# Sheet.net
KiCad netlist of a schematic drawn in Altium Designer
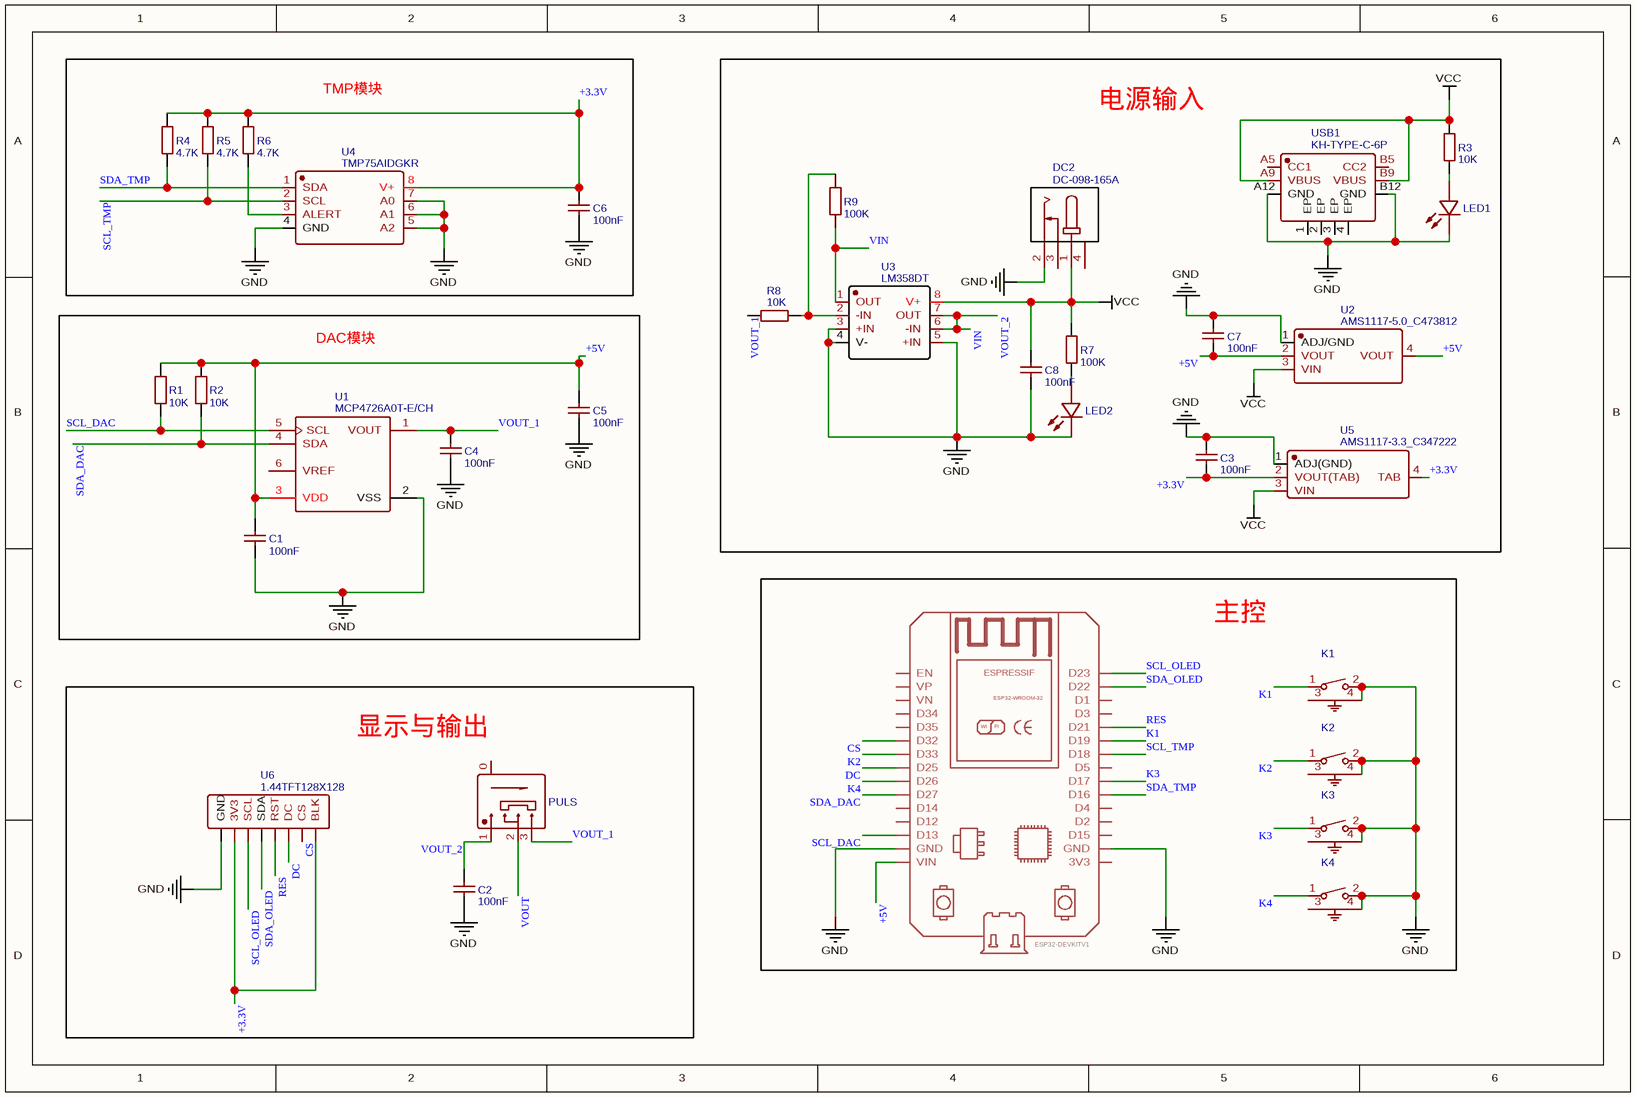
[diagram p0: Sheet.schdoc]

(export (version "E")
  (design (tool "Eeschema 10.0.6"))
  (components
    (comp (ref "BOARD1")
      (value "ESP32DEVKITV1")
      (fields (field (name "CONTRIBUTOR") "radio"))
      (libsource (lib "altium-import") (part "root_0_ESP32DEVKITV1_"))
    )
    (comp (ref "C1")
      (value "100nF")
      (fields
        (field (name "BOM_SUPPLIER PART") "C328914")
        (field (name "BOM_MANUFACTURER PART") "FN15X104K160PNG")
        (field (name "CONTRIBUTOR") "LCSC")
      )
      (libsource (lib "altium-import") (part "root_3_100nF_"))
    )
    (comp (ref "C2")
      (value "100nF")
      (fields
        (field (name "BOM_SUPPLIER PART") "C328914")
        (field (name "BOM_MANUFACTURER PART") "FN15X104K160PNG")
        (field (name "CONTRIBUTOR") "LCSC")
      )
      (libsource (lib "altium-import") (part "root_1_100nF_"))
    )
    (comp (ref "C3")
      (value "100nF")
      (fields
        (field (name "BOM_SUPPLIER PART") "C328914")
        (field (name "BOM_MANUFACTURER PART") "FN15X104K160PNG")
        (field (name "CONTRIBUTOR") "LCSC")
      )
      (libsource (lib "altium-import") (part "root_1_100nF_"))
    )
    (comp (ref "C4")
      (value "100nF")
      (fields
        (field (name "BOM_SUPPLIER PART") "C328914")
        (field (name "BOM_MANUFACTURER PART") "FN15X104K160PNG")
        (field (name "CONTRIBUTOR") "LCSC")
      )
      (libsource (lib "altium-import") (part "root_1_100nF_"))
    )
    (comp (ref "C5")
      (value "100nF")
      (fields
        (field (name "BOM_SUPPLIER PART") "C328914")
        (field (name "BOM_MANUFACTURER PART") "FN15X104K160PNG")
        (field (name "CONTRIBUTOR") "LCSC")
      )
      (libsource (lib "altium-import") (part "root_1_100nF_"))
    )
    (comp (ref "C6")
      (value "100nF")
      (fields
        (field (name "BOM_SUPPLIER PART") "C328914")
        (field (name "BOM_MANUFACTURER PART") "FN15X104K160PNG")
        (field (name "CONTRIBUTOR") "LCSC")
      )
      (libsource (lib "altium-import") (part "root_1_100nF_"))
    )
    (comp (ref "C7")
      (value "100nF")
      (fields
        (field (name "BOM_SUPPLIER PART") "C328914")
        (field (name "BOM_MANUFACTURER PART") "FN15X104K160PNG")
        (field (name "CONTRIBUTOR") "LCSC")
      )
      (libsource (lib "altium-import") (part "root_1_100nF_"))
    )
    (comp (ref "C8")
      (value "100nF")
      (fields
        (field (name "BOM_SUPPLIER PART") "C328914")
        (field (name "BOM_MANUFACTURER PART") "FN15X104K160PNG")
        (field (name "CONTRIBUTOR") "LCSC")
      )
      (libsource (lib "altium-import") (part "root_1_100nF_"))
    )
    (comp (ref "DC2")
      (value "DC-098-165A")
      (fields (field (name "BOM_SUPPLIER PART") "C129001") (field (name "CONTRIBUTOR") "LCSC"))
      (libsource (lib "altium-import") (part "root_3_DC-098-165A_"))
    )
    (comp (ref "K1")
      (value "KH-3635-CAJ")
      (fields (field (name "BOM_SUPPLIER PART") "C530670") (field (name "CONTRIBUTOR") "LCSC"))
      (libsource (lib "altium-import") (part "root_0_KH-3635-CAJ_"))
    )
    (comp (ref "K2")
      (value "KH-3635-CAJ")
      (fields (field (name "BOM_SUPPLIER PART") "C530670") (field (name "CONTRIBUTOR") "LCSC"))
      (libsource (lib "altium-import") (part "root_0_KH-3635-CAJ_"))
    )
    (comp (ref "K3")
      (value "KH-3635-CAJ")
      (fields (field (name "BOM_SUPPLIER PART") "C530670") (field (name "CONTRIBUTOR") "LCSC"))
      (libsource (lib "altium-import") (part "root_0_KH-3635-CAJ_"))
    )
    (comp (ref "K4")
      (value "KH-3635-CAJ")
      (fields (field (name "BOM_SUPPLIER PART") "C530670") (field (name "CONTRIBUTOR") "LCSC"))
      (libsource (lib "altium-import") (part "root_0_KH-3635-CAJ_"))
    )
    (comp (ref "LED1")
      (value "17-21SYGC/S530-E3/TR8")
      (fields (field (name "BOM_SUPPLIER PART") "C142303") (field (name "CONTRIBUTOR") "LCSC"))
      (libsource (lib "altium-import") (part "root_1_17-21SYGC/S530-E3/TR8_"))
    )
    (comp (ref "LED2")
      (value "17-21SURC/S530-A2/TR8")
      (fields (field (name "BOM_SUPPLIER PART") "C131244") (field (name "CONTRIBUTOR") "LCSC"))
      (libsource (lib "altium-import") (part "root_1_17-21SURC/S530-A2/TR8_"))
    )
    (comp (ref "PULS")
      (value "SK-3296S-01-L1")
      (fields (field (name "BOM_SUPPLIER PART") "C319020") (field (name "CONTRIBUTOR") "LCSC"))
      (libsource (lib "altium-import") (part "root_1_SK-3296S-01-L1_"))
    )
    (comp (ref "R1")
      (value "10K")
      (fields
        (field (name "BOM_MANUFACTURER PART") "0402WGJ0472TCE")
        (field (name "BOM_SUPPLIER PART") "C25940")
      )
      (libsource (lib "altium-import") (part "root_3_10K_"))
    )
    (comp (ref "R2")
      (value "10K")
      (fields
        (field (name "BOM_MANUFACTURER PART") "0402WGJ0472TCE")
        (field (name "BOM_SUPPLIER PART") "C25940")
      )
      (libsource (lib "altium-import") (part "root_1_10K_"))
    )
    (comp (ref "R3")
      (value "10K")
      (fields
        (field (name "BOM_MANUFACTURER PART") "0603WAF1002T5E")
        (field (name "BOM_SUPPLIER PART") "C25804")
      )
      (libsource (lib "altium-import") (part "root_1_10K_"))
    )
    (comp (ref "R4")
      (value "4.7K")
      (fields
        (field (name "BOM_MANUFACTURER PART") "0402WGJ0472TCE")
        (field (name "BOM_SUPPLIER PART") "C25940")
      )
      (libsource (lib "altium-import") (part "root_1_4.7K_"))
    )
    (comp (ref "R5")
      (value "4.7K")
      (fields
        (field (name "BOM_MANUFACTURER PART") "0402WGJ0472TCE")
        (field (name "BOM_SUPPLIER PART") "C25940")
      )
      (libsource (lib "altium-import") (part "root_1_4.7K_"))
    )
    (comp (ref "R6")
      (value "4.7K")
      (fields
        (field (name "BOM_MANUFACTURER PART") "0402WGJ0472TCE")
        (field (name "BOM_SUPPLIER PART") "C25940")
      )
      (libsource (lib "altium-import") (part "root_1_4.7K_"))
    )
    (comp (ref "R7")
      (value "100K")
      (fields
        (field (name "BOM_MANUFACTURER PART") "0603WAJ0104T5E")
        (field (name "BOM_SUPPLIER PART") "C15458")
      )
      (libsource (lib "altium-import") (part "root_1_100K_"))
    )
    (comp (ref "R8")
      (value "10K")
      (fields
        (field (name "BOM_MANUFACTURER PART") "0603WAF1002T5E")
        (field (name "BOM_SUPPLIER PART") "C25804")
      )
      (libsource (lib "altium-import") (part "root_2_10K_"))
    )
    (comp (ref "R9")
      (value "100K")
      (fields
        (field (name "BOM_MANUFACTURER PART") "0603WAJ0104T5E")
        (field (name "BOM_SUPPLIER PART") "C15458")
      )
      (libsource (lib "altium-import") (part "root_1_100K_"))
    )
    (comp (ref "U1")
      (value "MCP4726A0T-E/CH")
      (fields (field (name "BOM_SUPPLIER PART") "C191581") (field (name "CONTRIBUTOR") "LCSC"))
      (libsource (lib "altium-import") (part "root_0_MCP4726A0T-E/CH_"))
    )
    (comp (ref "U2")
      (value "AMS1117-5.0_C473812")
      (fields
        (field (name "BOM_SUPPLIER PART") "C473812")
        (field (name "BOM_MANUFACTURER PART") "AMS1117-5.0")
        (field (name "CONTRIBUTOR") "LCSC")
      )
      (libsource (lib "altium-import") (part "root_0_AMS1117-5.0_C473812_"))
    )
    (comp (ref "U3")
      (value "LM358DT")
      (fields (field (name "BOM_SUPPLIER PART") "C9418"))
      (libsource (lib "altium-import") (part "root_0_LM358DT_"))
    )
    (comp (ref "U4")
      (value "TMP75AIDGKR")
      (fields (field (name "BOM_SUPPLIER PART") "C105258") (field (name "CONTRIBUTOR") "LCSC"))
      (libsource (lib "altium-import") (part "root_0_TMP75AIDGKR_"))
    )
    (comp (ref "U5")
      (value "AMS1117-3.3_C347222")
      (fields
        (field (name "BOM_SUPPLIER PART") "C347222")
        (field (name "BOM_MANUFACTURER PART") "AMS1117-3.3")
        (field (name "CONTRIBUTOR") "LCSC")
      )
      (libsource (lib "altium-import") (part "root_0_AMS1117-3.3_C347222_"))
    )
    (comp (ref "U6")
      (value "1.44TFT128X128")
      (fields (field (name "CONTRIBUTOR") "IoT-J"))
      (libsource (lib "altium-import") (part "root_1_1.44TFT128X128_"))
    )
    (comp (ref "USB1")
      (value "KH-TYPE-C-6P")
      (fields (field (name "BOM_SUPPLIER PART") "C709355") (field (name "CONTRIBUTOR") "LCSC"))
      (libsource (lib "altium-import") (part "root_0_KH-TYPE-C-6P_"))
    )
  )
  (nets
    (net (code "1") (name "/+3.3V") (class "Default")
      (node (ref "C3") (pin "1") (pinfunction "1_1") (pintype "passive"))
      (node (ref "C6") (pin "2") (pinfunction "2_2") (pintype "passive"))
      (node (ref "R4") (pin "2") (pinfunction "2_2") (pintype "passive"))
      (node (ref "R5") (pin "2") (pinfunction "2_2") (pintype "passive"))
      (node (ref "R6") (pin "2") (pinfunction "2_2") (pintype "passive"))
      (node (ref "U4") (pin "8") (pinfunction "V+_8") (pintype "passive"))
      (node (ref "U5") (pin "2") (pinfunction "VOUT(TAB)_2") (pintype "passive"))
      (node (ref "U5") (pin "4") (pinfunction "TAB_4") (pintype "passive"))
      (node (ref "U6") (pin "2") (pinfunction "3V3_2") (pintype "passive"))
      (node (ref "U6") (pin "8") (pinfunction "BLK_8") (pintype "passive"))
    )
    (net (code "2") (name "/+5V") (class "Default")
      (node (ref "BOARD1") (pin "VIN") (pinfunction "VIN_VIN") (pintype "passive"))
      (node (ref "C1") (pin "1") (pinfunction "1_1") (pintype "passive"))
      (node (ref "C5") (pin "2") (pinfunction "2_2") (pintype "passive"))
      (node (ref "C7") (pin "1") (pinfunction "1_1") (pintype "passive"))
      (node (ref "R1") (pin "1") (pinfunction "1_1") (pintype "passive"))
      (node (ref "R2") (pin "2") (pinfunction "2_2") (pintype "passive"))
      (node (ref "U1") (pin "3") (pinfunction "VDD_3") (pintype "passive"))
      (node (ref "U2") (pin "2") (pinfunction "VOUT_2") (pintype "passive"))
      (node (ref "U2") (pin "4") (pinfunction "VOUT_4") (pintype "passive"))
    )
    (net (code "3") (name "/CS") (class "Default")
      (node (ref "BOARD1") (pin "D32") (pinfunction "D32_D32") (pintype "passive"))
      (node (ref "U6") (pin "7") (pinfunction "CS_7") (pintype "passive"))
    )
    (net (code "4") (name "/DC") (class "Default")
      (node (ref "BOARD1") (pin "D25") (pinfunction "D25_D25") (pintype "passive"))
      (node (ref "U6") (pin "6") (pinfunction "DC_6") (pintype "passive"))
    )
    (net (code "5") (name "/K1") (class "Default")
      (node (ref "BOARD1") (pin "D19") (pinfunction "D19_D19") (pintype "passive"))
      (node (ref "K1") (pin "1") (pinfunction "C_1") (pintype "passive"))
    )
    (net (code "6") (name "/K2") (class "Default")
      (node (ref "BOARD1") (pin "D33") (pinfunction "D33_D33") (pintype "passive"))
      (node (ref "K2") (pin "1") (pinfunction "C_1") (pintype "passive"))
    )
    (net (code "7") (name "/K3") (class "Default")
      (node (ref "BOARD1") (pin "D17") (pinfunction "D17_D17") (pintype "passive"))
      (node (ref "K3") (pin "1") (pinfunction "C_1") (pintype "passive"))
    )
    (net (code "8") (name "/K4") (class "Default")
      (node (ref "BOARD1") (pin "D26") (pinfunction "D26_D26") (pintype "passive"))
      (node (ref "K4") (pin "1") (pinfunction "C_1") (pintype "passive"))
    )
    (net (code "9") (name "/RES") (class "Default")
      (node (ref "BOARD1") (pin "D21") (pinfunction "D21_D21") (pintype "passive"))
      (node (ref "U6") (pin "5") (pinfunction "RST_5") (pintype "passive"))
    )
    (net (code "10") (name "/SCL_DAC") (class "Default")
      (node (ref "BOARD1") (pin "D13") (pinfunction "D13_D13") (pintype "passive"))
      (node (ref "R1") (pin "2") (pinfunction "2_2") (pintype "passive"))
      (node (ref "U1") (pin "5") (pinfunction "SCL_5") (pintype "passive"))
    )
    (net (code "11") (name "/SCL_OLED") (class "Default")
      (node (ref "BOARD1") (pin "D23") (pinfunction "D23_D23") (pintype "passive"))
      (node (ref "U6") (pin "3") (pinfunction "SCL_3") (pintype "passive"))
    )
    (net (code "12") (name "/SCL_TMP") (class "Default")
      (node (ref "BOARD1") (pin "D18") (pinfunction "D18_D18") (pintype "passive"))
      (node (ref "R5") (pin "1") (pinfunction "1_1") (pintype "passive"))
      (node (ref "U4") (pin "2") (pinfunction "SCL_2") (pintype "passive"))
    )
    (net (code "13") (name "/SDA_DAC") (class "Default")
      (node (ref "BOARD1") (pin "D27") (pinfunction "D27_D27") (pintype "passive"))
      (node (ref "R2") (pin "1") (pinfunction "1_1") (pintype "passive"))
      (node (ref "U1") (pin "4") (pinfunction "SDA_4") (pintype "passive"))
    )
    (net (code "14") (name "/SDA_OLED") (class "Default")
      (node (ref "BOARD1") (pin "D22") (pinfunction "D22_D22") (pintype "passive"))
      (node (ref "U6") (pin "4") (pinfunction "SDA_4") (pintype "passive"))
    )
    (net (code "15") (name "/SDA_TMP") (class "Default")
      (node (ref "BOARD1") (pin "D16") (pinfunction "D16_D16") (pintype "passive"))
      (node (ref "R4") (pin "1") (pinfunction "1_1") (pintype "passive"))
      (node (ref "U4") (pin "1") (pinfunction "SDA_1") (pintype "passive"))
    )
    (net (code "16") (name "/VIN") (class "Default")
      (node (ref "C2") (pin "2") (pinfunction "2_2") (pintype "passive"))
      (node (ref "PULS") (pin "1") (pinfunction "1_1") (pintype "passive"))
      (node (ref "R9") (pin "1") (pinfunction "1_1") (pintype "passive"))
      (node (ref "U3") (pin "1") (pinfunction "OUT_1") (pintype "passive"))
      (node (ref "U3") (pin "6") (pinfunction "-IN_6") (pintype "passive"))
      (node (ref "U3") (pin "7") (pinfunction "OUT_7") (pintype "passive"))
    )
    (net (code "17") (name "/VOUT") (class "Default")
      (node (ref "PULS") (pin "2") (pinfunction "2_2") (pintype "passive"))
    )
    (net (code "18") (name "/VOUT_1") (class "Default")
      (node (ref "C4") (pin "2") (pinfunction "2_2") (pintype "passive"))
      (node (ref "PULS") (pin "3") (pinfunction "3_3") (pintype "passive"))
      (node (ref "R8") (pin "2") (pinfunction "2_2") (pintype "passive"))
      (node (ref "U1") (pin "1") (pinfunction "VOUT_1") (pintype "passive"))
    )
    (net (code "19") (name "GND") (class "Default")
      (node (ref "BOARD1") (pin "GND") (pinfunction "GND_GND") (pintype "passive"))
      (node (ref "BOARD1") (pin "GND@1") (pinfunction "GND_GND@1") (pintype "passive"))
      (node (ref "C1") (pin "2") (pinfunction "2_2") (pintype "passive"))
      (node (ref "C2") (pin "1") (pinfunction "1_1") (pintype "passive"))
      (node (ref "C3") (pin "2") (pinfunction "2_2") (pintype "passive"))
      (node (ref "C4") (pin "1") (pinfunction "1_1") (pintype "passive"))
      (node (ref "C5") (pin "1") (pinfunction "1_1") (pintype "passive"))
      (node (ref "C6") (pin "1") (pinfunction "1_1") (pintype "passive"))
      (node (ref "C7") (pin "2") (pinfunction "2_2") (pintype "passive"))
      (node (ref "C8") (pin "1") (pinfunction "1_1") (pintype "passive"))
      (node (ref "DC2") (pin "2") (pinfunction "2_2") (pintype "passive"))
      (node (ref "K1") (pin "2") (pinfunction "D_2") (pintype "passive"))
      (node (ref "K1") (pin "4") (pinfunction "B_4") (pintype "passive"))
      (node (ref "K2") (pin "2") (pinfunction "D_2") (pintype "passive"))
      (node (ref "K2") (pin "4") (pinfunction "B_4") (pintype "passive"))
      (node (ref "K3") (pin "2") (pinfunction "D_2") (pintype "passive"))
      (node (ref "K3") (pin "4") (pinfunction "B_4") (pintype "passive"))
      (node (ref "K4") (pin "2") (pinfunction "D_2") (pintype "passive"))
      (node (ref "K4") (pin "4") (pinfunction "B_4") (pintype "passive"))
      (node (ref "LED1") (pin "1") (pinfunction "K_1") (pintype "passive"))
      (node (ref "LED2") (pin "1") (pinfunction "K_1") (pintype "passive"))
      (node (ref "U1") (pin "2") (pinfunction "VSS_2") (pintype "passive"))
      (node (ref "U2") (pin "1") (pinfunction "ADJ/GND_1") (pintype "passive"))
      (node (ref "U3") (pin "3") (pinfunction "+IN_3") (pintype "passive"))
      (node (ref "U3") (pin "4") (pinfunction "V-_4") (pintype "passive"))
      (node (ref "U3") (pin "5") (pinfunction "+IN_5") (pintype "passive"))
      (node (ref "U4") (pin "4") (pinfunction "GND_4") (pintype "passive"))
      (node (ref "U4") (pin "5") (pinfunction "A2_5") (pintype "passive"))
      (node (ref "U4") (pin "6") (pinfunction "A1_6") (pintype "passive"))
      (node (ref "U4") (pin "7") (pinfunction "A0_7") (pintype "passive"))
      (node (ref "U5") (pin "1") (pinfunction "ADJ(GND)_1") (pintype "passive"))
      (node (ref "U6") (pin "1") (pinfunction "GND_1") (pintype "passive"))
      (node (ref "USB1") (pin "A12") (pinfunction "GND_A12") (pintype "passive"))
      (node (ref "USB1") (pin "B12") (pinfunction "GND_B12") (pintype "passive"))
    )
    (net (code "20") (name "Net-(LED1-A)") (class "Default")
      (node (ref "LED1") (pin "2") (pinfunction "A_2") (pintype "passive"))
      (node (ref "R3") (pin "1") (pinfunction "1_1") (pintype "passive"))
    )
    (net (code "21") (name "Net-(LED2-A)") (class "Default")
      (node (ref "LED2") (pin "2") (pinfunction "A_2") (pintype "passive"))
      (node (ref "R7") (pin "1") (pinfunction "1_1") (pintype "passive"))
    )
    (net (code "22") (name "Net-(R8-Pad1)") (class "Default")
      (node (ref "R8") (pin "1") (pinfunction "1_1") (pintype "passive"))
      (node (ref "R9") (pin "2") (pinfunction "2_2") (pintype "passive"))
      (node (ref "U3") (pin "2") (pinfunction "-IN_2") (pintype "passive"))
    )
    (net (code "23") (name "Net-(U4-ALERT)") (class "Default")
      (node (ref "R6") (pin "1") (pinfunction "1_1") (pintype "passive"))
      (node (ref "U4") (pin "3") (pinfunction "ALERT_3") (pintype "passive"))
    )
    (net (code "24") (name "VCC") (class "Default")
      (node (ref "C8") (pin "2") (pinfunction "2_2") (pintype "passive"))
      (node (ref "DC2") (pin "1") (pinfunction "1_1") (pintype "passive"))
      (node (ref "R3") (pin "2") (pinfunction "2_2") (pintype "passive"))
      (node (ref "R7") (pin "2") (pinfunction "2_2") (pintype "passive"))
      (node (ref "U2") (pin "3") (pinfunction "VIN_3") (pintype "passive"))
      (node (ref "U3") (pin "8") (pinfunction "V+_8") (pintype "passive"))
      (node (ref "U5") (pin "3") (pinfunction "VIN_3") (pintype "passive"))
      (node (ref "USB1") (pin "A9") (pinfunction "VBUS_A9") (pintype "passive"))
      (node (ref "USB1") (pin "B9") (pinfunction "VBUS_B9") (pintype "passive"))
    )
    (net (code "25") (name "unconnected-(BOARD1-Pad3V3)") (class "Default")
      (node (ref "BOARD1") (pin "3V3") (pinfunction "3V3_3V3") (pintype "passive"))
    )
    (net (code "26") (name "unconnected-(BOARD1-PadD1)") (class "Default")
      (node (ref "BOARD1") (pin "D1") (pinfunction "D1_D1") (pintype "passive"))
    )
    (net (code "27") (name "unconnected-(BOARD1-PadD2)") (class "Default")
      (node (ref "BOARD1") (pin "D2") (pinfunction "D2_D2") (pintype "passive"))
    )
    (net (code "28") (name "unconnected-(BOARD1-PadD3)") (class "Default")
      (node (ref "BOARD1") (pin "D3") (pinfunction "D3_D3") (pintype "passive"))
    )
    (net (code "29") (name "unconnected-(BOARD1-PadD4)") (class "Default")
      (node (ref "BOARD1") (pin "D4") (pinfunction "D4_D4") (pintype "passive"))
    )
    (net (code "30") (name "unconnected-(BOARD1-PadD5)") (class "Default")
      (node (ref "BOARD1") (pin "D5") (pinfunction "D5_D5") (pintype "passive"))
    )
    (net (code "31") (name "unconnected-(BOARD1-PadD12)") (class "Default")
      (node (ref "BOARD1") (pin "D12") (pinfunction "D12_D12") (pintype "passive"))
    )
    (net (code "32") (name "unconnected-(BOARD1-PadD14)") (class "Default")
      (node (ref "BOARD1") (pin "D14") (pinfunction "D14_D14") (pintype "passive"))
    )
    (net (code "33") (name "unconnected-(BOARD1-PadD15)") (class "Default")
      (node (ref "BOARD1") (pin "D15") (pinfunction "D15_D15") (pintype "passive"))
    )
    (net (code "34") (name "unconnected-(BOARD1-PadD34)") (class "Default")
      (node (ref "BOARD1") (pin "D34") (pinfunction "D34_D34") (pintype "passive"))
    )
    (net (code "35") (name "unconnected-(BOARD1-PadD35)") (class "Default")
      (node (ref "BOARD1") (pin "D35") (pinfunction "D35_D35") (pintype "passive"))
    )
    (net (code "36") (name "unconnected-(BOARD1-PadEN)") (class "Default")
      (node (ref "BOARD1") (pin "EN") (pinfunction "EN_EN") (pintype "passive"))
    )
    (net (code "37") (name "unconnected-(BOARD1-PadVN)") (class "Default")
      (node (ref "BOARD1") (pin "VN") (pinfunction "VN_VN") (pintype "passive"))
    )
    (net (code "38") (name "unconnected-(BOARD1-PadVP)") (class "Default")
      (node (ref "BOARD1") (pin "VP") (pinfunction "VP_VP") (pintype "passive"))
    )
    (net (code "39") (name "unconnected-(DC2-Pad3)") (class "Default")
      (node (ref "DC2") (pin "3") (pinfunction "3_3") (pintype "passive"))
    )
    (net (code "40") (name "unconnected-(DC2-Pad4)") (class "Default")
      (node (ref "DC2") (pin "4") (pinfunction "4_4") (pintype "passive"))
    )
    (net (code "41") (name "unconnected-(K1-A-Pad3)") (class "Default")
      (node (ref "K1") (pin "3") (pinfunction "A_3") (pintype "passive"))
    )
    (net (code "42") (name "unconnected-(K2-A-Pad3)") (class "Default")
      (node (ref "K2") (pin "3") (pinfunction "A_3") (pintype "passive"))
    )
    (net (code "43") (name "unconnected-(K3-A-Pad3)") (class "Default")
      (node (ref "K3") (pin "3") (pinfunction "A_3") (pintype "passive"))
    )
    (net (code "44") (name "unconnected-(K4-A-Pad3)") (class "Default")
      (node (ref "K4") (pin "3") (pinfunction "A_3") (pintype "passive"))
    )
    (net (code "45") (name "unconnected-(PULS-Pad0)") (class "Default")
      (node (ref "PULS") (pin "0") (pinfunction "0_0") (pintype "passive"))
    )
    (net (code "46") (name "unconnected-(U1-VREF-Pad6)") (class "Default")
      (node (ref "U1") (pin "6") (pinfunction "VREF_6") (pintype "passive"))
    )
    (net (code "47") (name "unconnected-(USB1-CC1-PadA5)") (class "Default")
      (node (ref "USB1") (pin "A5") (pinfunction "CC1_A5") (pintype "passive"))
    )
    (net (code "48") (name "unconnected-(USB1-CC2-PadB5)") (class "Default")
      (node (ref "USB1") (pin "B5") (pinfunction "CC2_B5") (pintype "passive"))
    )
    (net (code "49") (name "unconnected-(USB1-EP-Pad1)") (class "Default")
      (node (ref "USB1") (pin "1") (pinfunction "EP_1") (pintype "passive"))
    )
    (net (code "50") (name "unconnected-(USB1-EP-Pad2)") (class "Default")
      (node (ref "USB1") (pin "2") (pinfunction "EP_2") (pintype "passive"))
    )
    (net (code "51") (name "unconnected-(USB1-EP-Pad3)") (class "Default")
      (node (ref "USB1") (pin "3") (pinfunction "EP_3") (pintype "passive"))
    )
    (net (code "52") (name "unconnected-(USB1-EP-Pad4)") (class "Default")
      (node (ref "USB1") (pin "4") (pinfunction "EP_4") (pintype "passive"))
    )
  )
)
